# OpenAir.net
KiCad netlist of a schematic drawn in EAGLE
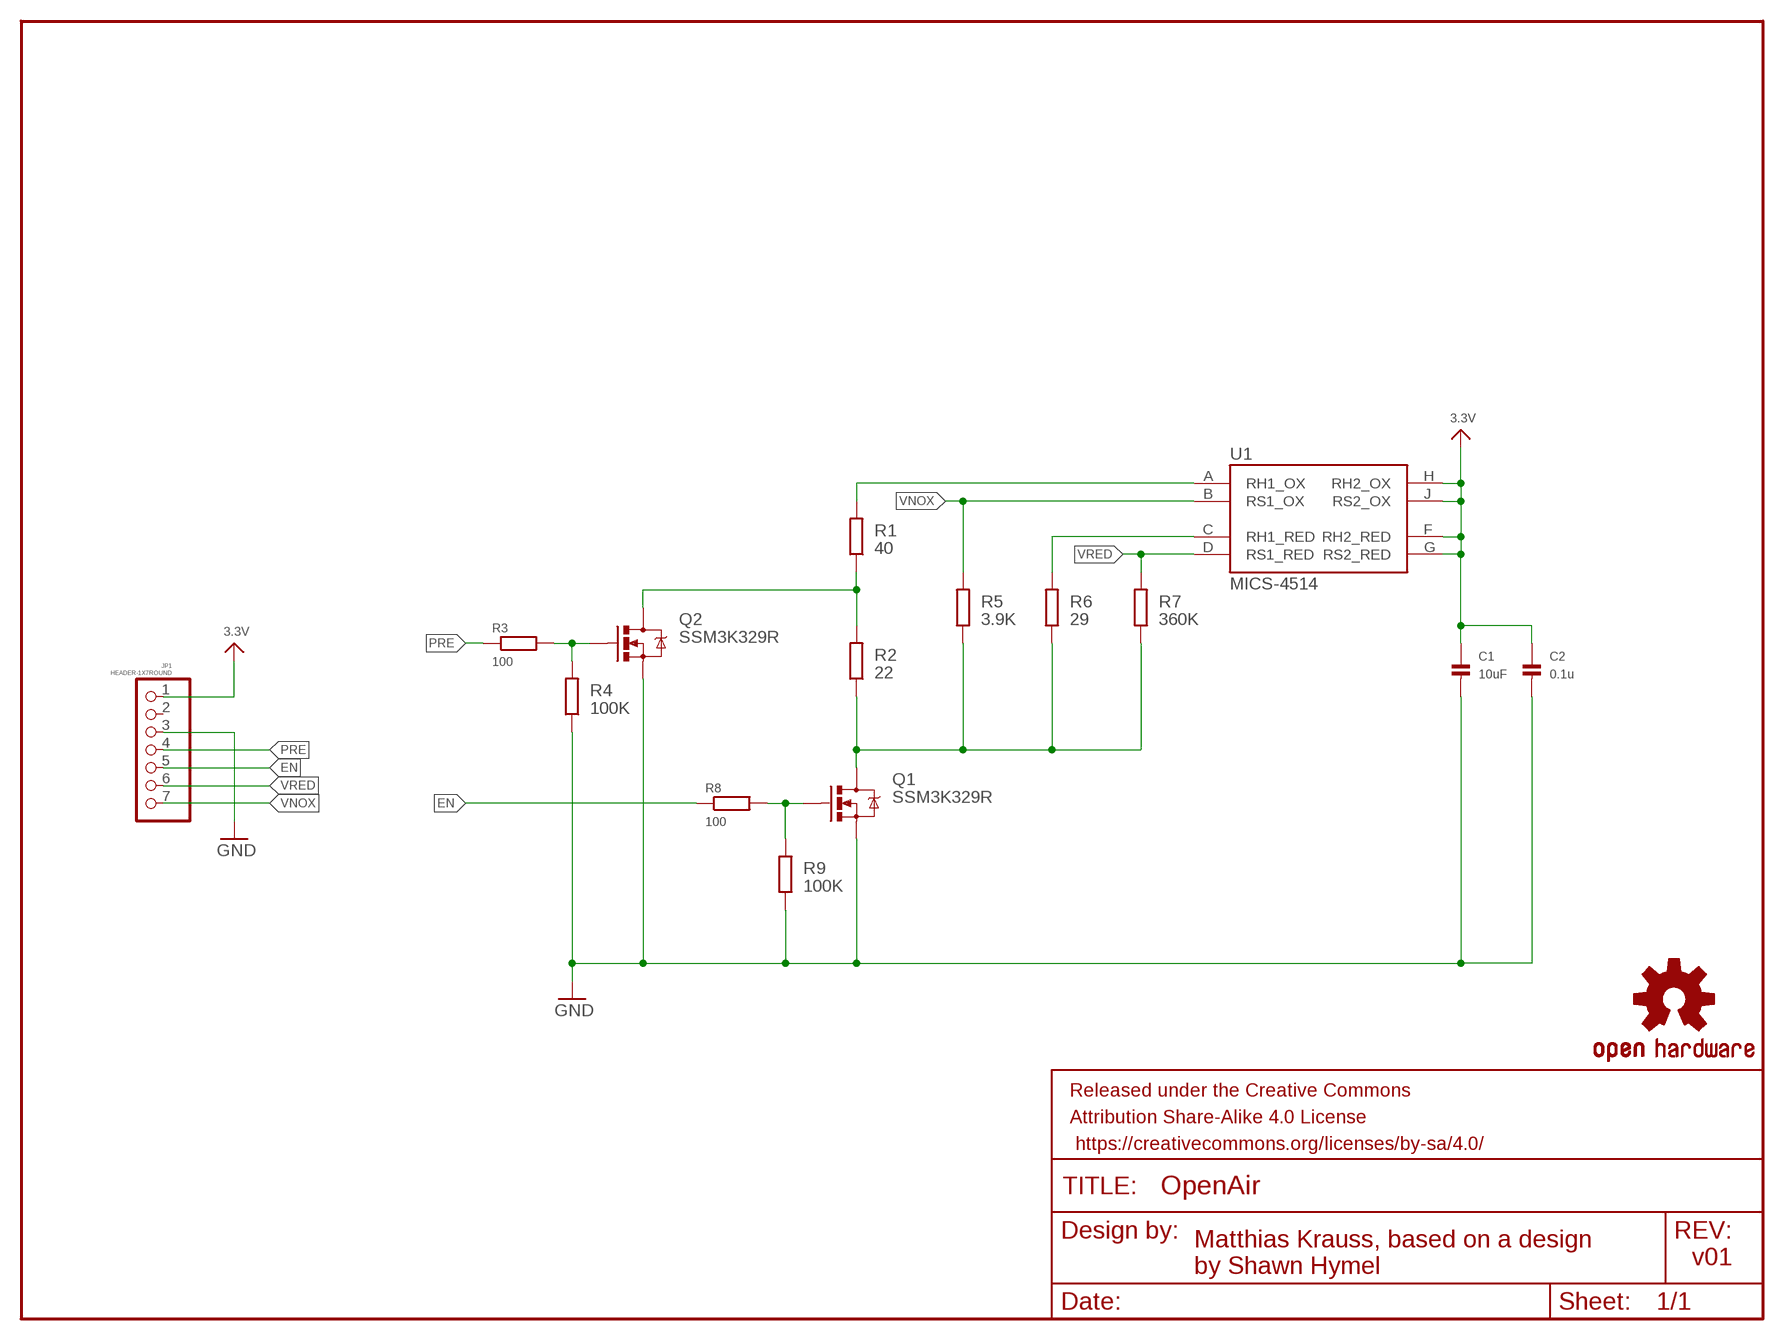
[diagram p0: schematic, sheet 1]

(export (version "E")
  (design (tool "Eeschema 10.0.6"))
  (components
    (comp (ref "C1")
      (value "10uF")
      (footprint "eagle-import:0603")
      (libsource (lib "eagle-import") (part "CAP_CERAMIC0603"))
    )
    (comp (ref "C2")
      (value "0.1u")
      (footprint "eagle-import:0603")
      (libsource (lib "eagle-import") (part "CAP_CERAMIC0603"))
    )
    (comp (ref "FRAME1")
      (value "FRAME-LETTER")
      (footprint "eagle-import:CREATIVE_COMMONS")
      (libsource (lib "eagle-import") (part "FRAME-LETTER"))
    )
    (comp (ref "JP1")
      (value "HEADER-1X7ROUND")
      (footprint "eagle-import:1X07_ROUND")
      (libsource (lib "eagle-import") (part "HEADER-1X7ROUND"))
    )
    (comp (ref "LOGO1")
      (value "OSHW-LOGOS")
      (footprint "eagle-import:OSHW-LOGO-S")
      (libsource (lib "eagle-import") (part "OSHW-LOGOS"))
    )
    (comp (ref "Q1")
      (value "SSM3K329R")
      (footprint "eagle-import:SOT23-3")
      (fields (field (name "P_NAME") "BSS138"))
      (libsource (lib "eagle-import") (part "MOSFET-NCHANNELBSS138"))
    )
    (comp (ref "Q2")
      (value "SSM3K329R")
      (footprint "eagle-import:SOT23-3")
      (fields (field (name "P_NAME") "BSS138"))
      (libsource (lib "eagle-import") (part "MOSFET-NCHANNELBSS138"))
    )
    (comp (ref "R1")
      (value "40")
      (footprint "eagle-import:0603")
      (libsource (lib "eagle-import") (part "R-EU_0603"))
    )
    (comp (ref "R2")
      (value "22")
      (footprint "eagle-import:0603")
      (libsource (lib "eagle-import") (part "R-EU_0603"))
    )
    (comp (ref "R3")
      (value "100")
      (footprint "eagle-import:0603")
      (libsource (lib "eagle-import") (part "R-EU_0603"))
    )
    (comp (ref "R4")
      (value "100K")
      (footprint "eagle-import:0603")
      (libsource (lib "eagle-import") (part "R-EU_0603"))
    )
    (comp (ref "R5")
      (value "3.9K")
      (footprint "eagle-import:0603")
      (libsource (lib "eagle-import") (part "R-EU_0603"))
    )
    (comp (ref "R6")
      (value "29")
      (footprint "eagle-import:0603")
      (libsource (lib "eagle-import") (part "R-EU_0603"))
    )
    (comp (ref "R7")
      (value "360K")
      (footprint "eagle-import:0603")
      (libsource (lib "eagle-import") (part "R-EU_0603"))
    )
    (comp (ref "R8")
      (value "100")
      (footprint "eagle-import:0603")
      (libsource (lib "eagle-import") (part "R-EU_0603"))
    )
    (comp (ref "R9")
      (value "100K")
      (footprint "eagle-import:0603")
      (libsource (lib "eagle-import") (part "R-EU_0603"))
    )
    (comp (ref "U1")
      (value "MICS-4514")
      (footprint "eagle-import:MICS_10-SMD")
      (libsource (lib "eagle-import") (part "MICS-4514"))
    )
  )
  (nets
    (net (code "1") (name "3.3V") (class "Default")
      (node (ref "C1") (pin "1") (pinfunction "P$1_1") (pintype "passive"))
      (node (ref "C2") (pin "1") (pinfunction "P$1_1") (pintype "passive"))
      (node (ref "JP1") (pin "1") (pinfunction "1_1") (pintype "passive"))
      (node (ref "U1") (pin "F") (pinfunction "RH2_RED_F") (pintype "bidirectional"))
      (node (ref "U1") (pin "G") (pinfunction "RS2_RED_G") (pintype "bidirectional"))
      (node (ref "U1") (pin "H") (pinfunction "RH2_OX_H") (pintype "bidirectional"))
      (node (ref "U1") (pin "J") (pinfunction "RS2_OX_J") (pintype "bidirectional"))
    )
    (net (code "2") (name "EN") (class "Default")
      (node (ref "JP1") (pin "5") (pinfunction "5_5") (pintype "passive"))
      (node (ref "R8") (pin "1") (pinfunction "1_1") (pintype "passive"))
    )
    (net (code "3") (name "GND") (class "Default")
      (node (ref "C1") (pin "2") (pinfunction "P$2_2") (pintype "passive"))
      (node (ref "C2") (pin "2") (pinfunction "P$2_2") (pintype "passive"))
      (node (ref "JP1") (pin "3") (pinfunction "3_3") (pintype "passive"))
      (node (ref "Q1") (pin "2") (pinfunction "S_2") (pintype "passive"))
      (node (ref "Q2") (pin "2") (pinfunction "S_2") (pintype "passive"))
      (node (ref "R4") (pin "1") (pinfunction "1_1") (pintype "passive"))
      (node (ref "R9") (pin "1") (pinfunction "1_1") (pintype "passive"))
    )
    (net (code "4") (name "Net-(Q1-D)") (class "Default")
      (node (ref "Q1") (pin "3") (pinfunction "D_3") (pintype "passive"))
      (node (ref "R2") (pin "1") (pinfunction "1_1") (pintype "passive"))
      (node (ref "R5") (pin "1") (pinfunction "1_1") (pintype "passive"))
      (node (ref "R6") (pin "1") (pinfunction "1_1") (pintype "passive"))
      (node (ref "R7") (pin "1") (pinfunction "1_1") (pintype "passive"))
    )
    (net (code "5") (name "Net-(Q1-G)") (class "Default")
      (node (ref "Q1") (pin "1") (pinfunction "G_1") (pintype "passive"))
      (node (ref "R8") (pin "2") (pinfunction "2_2") (pintype "passive"))
      (node (ref "R9") (pin "2") (pinfunction "2_2") (pintype "passive"))
    )
    (net (code "6") (name "Net-(Q2-D)") (class "Default")
      (node (ref "Q2") (pin "3") (pinfunction "D_3") (pintype "passive"))
      (node (ref "R1") (pin "1") (pinfunction "1_1") (pintype "passive"))
      (node (ref "R2") (pin "2") (pinfunction "2_2") (pintype "passive"))
    )
    (net (code "7") (name "Net-(Q2-G)") (class "Default")
      (node (ref "Q2") (pin "1") (pinfunction "G_1") (pintype "passive"))
      (node (ref "R3") (pin "2") (pinfunction "2_2") (pintype "passive"))
      (node (ref "R4") (pin "2") (pinfunction "2_2") (pintype "passive"))
    )
    (net (code "8") (name "Net-(U1-RH1_OX)") (class "Default")
      (node (ref "R1") (pin "2") (pinfunction "2_2") (pintype "passive"))
      (node (ref "U1") (pin "A") (pinfunction "RH1_OX_A") (pintype "bidirectional"))
    )
    (net (code "9") (name "Net-(U1-RH1_RED)") (class "Default")
      (node (ref "R6") (pin "2") (pinfunction "2_2") (pintype "passive"))
      (node (ref "U1") (pin "C") (pinfunction "RH1_RED_C") (pintype "bidirectional"))
    )
    (net (code "10") (name "PRE") (class "Default")
      (node (ref "JP1") (pin "4") (pinfunction "4_4") (pintype "passive"))
      (node (ref "R3") (pin "1") (pinfunction "1_1") (pintype "passive"))
    )
    (net (code "11") (name "VNOX") (class "Default")
      (node (ref "JP1") (pin "7") (pinfunction "7_7") (pintype "passive"))
      (node (ref "R5") (pin "2") (pinfunction "2_2") (pintype "passive"))
      (node (ref "U1") (pin "B") (pinfunction "RS1_OX_B") (pintype "bidirectional"))
    )
    (net (code "12") (name "VRED") (class "Default")
      (node (ref "JP1") (pin "6") (pinfunction "6_6") (pintype "passive"))
      (node (ref "R7") (pin "2") (pinfunction "2_2") (pintype "passive"))
      (node (ref "U1") (pin "D") (pinfunction "RS1_RED_D") (pintype "bidirectional"))
    )
    (net (code "13") (name "unconnected-(JP1-Pad2)") (class "Default")
      (node (ref "JP1") (pin "2") (pinfunction "2_2") (pintype "passive"))
    )
  )
)
